# Sychronome_driver.net
KiCad netlist of a schematic drawn in EAGLE
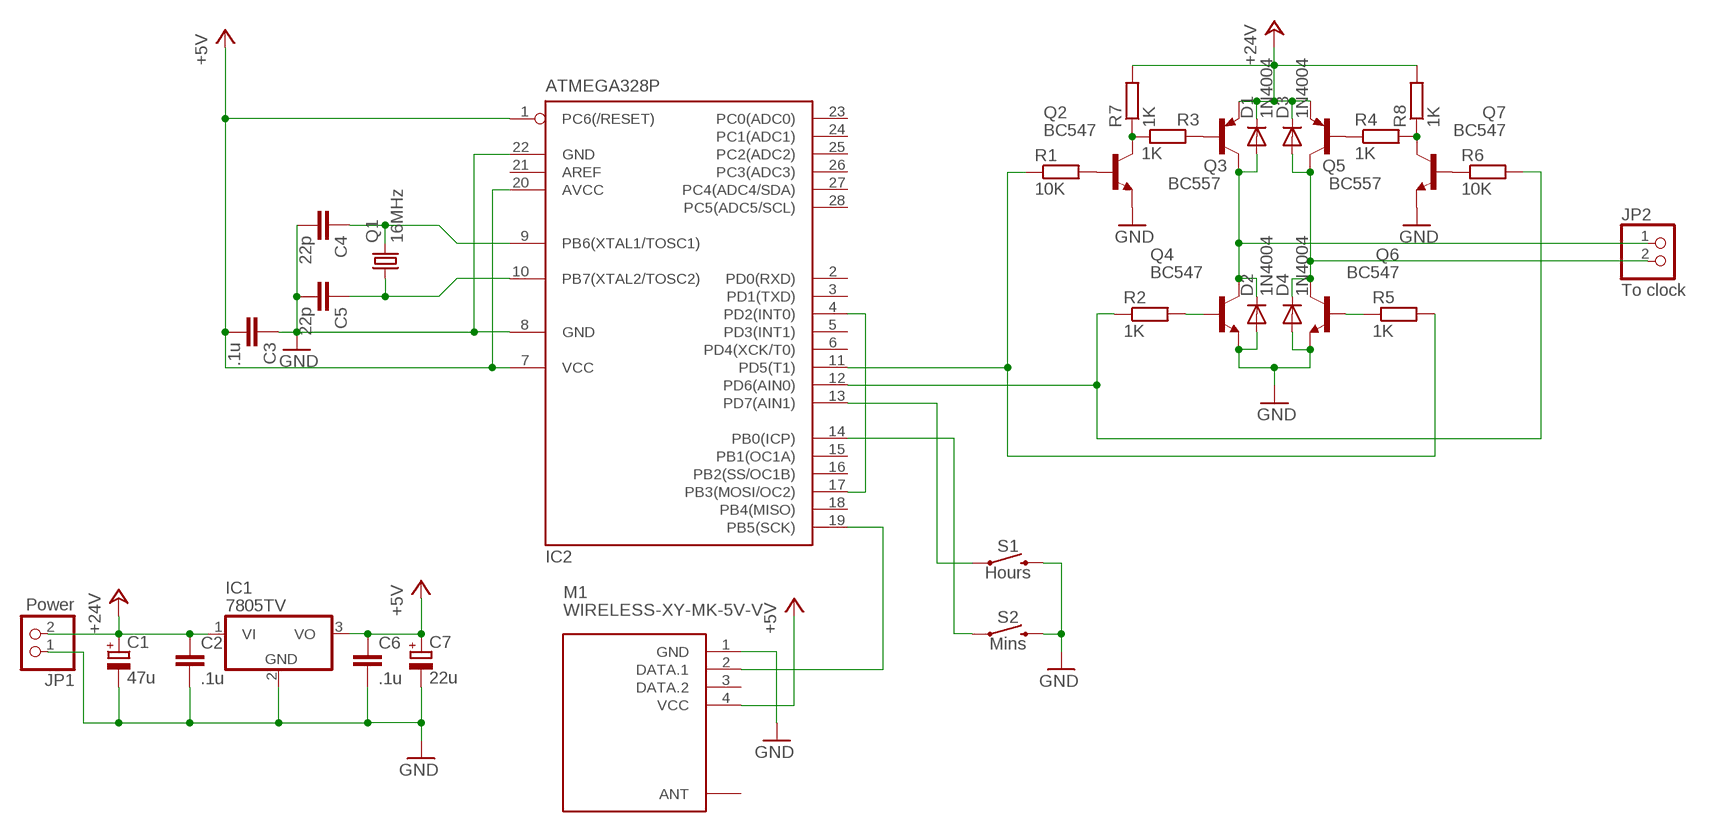
[diagram p0: schematic, sheet 1]

(export (version "E")
  (design (tool "Eeschema 10.0.6"))
  (components
    (comp (ref "C1")
      (value "47u")
      (footprint "eagle-import:E2,5-7")
      (libsource (lib "eagle-import") (part "CPOL-EUE2.5-7"))
    )
    (comp (ref "C2")
      (value ".1u")
      (footprint "eagle-import:C025-024X044")
      (libsource (lib "eagle-import") (part "C-EU025-024X044"))
    )
    (comp (ref "C3")
      (value ".1u")
      (footprint "eagle-import:C025-024X044")
      (libsource (lib "eagle-import") (part "C-EU025-024X044"))
    )
    (comp (ref "C4")
      (value "22p")
      (footprint "eagle-import:C025-024X044")
      (libsource (lib "eagle-import") (part "C-EU025-024X044"))
    )
    (comp (ref "C5")
      (value "22p")
      (footprint "eagle-import:C025-024X044")
      (libsource (lib "eagle-import") (part "C-EU025-024X044"))
    )
    (comp (ref "C6")
      (value ".1u")
      (footprint "eagle-import:C025-024X044")
      (libsource (lib "eagle-import") (part "C-EU025-024X044"))
    )
    (comp (ref "C7")
      (value "22u")
      (footprint "eagle-import:E2,5-7")
      (libsource (lib "eagle-import") (part "CPOL-EUE2.5-7"))
    )
    (comp (ref "D1")
      (value "1N4004")
      (footprint "eagle-import:DO41-10")
      (libsource (lib "eagle-import") (part "1N4004"))
    )
    (comp (ref "D2")
      (value "1N4004")
      (footprint "eagle-import:DO41-10")
      (libsource (lib "eagle-import") (part "1N4004"))
    )
    (comp (ref "D3")
      (value "1N4004")
      (footprint "eagle-import:DO41-10")
      (libsource (lib "eagle-import") (part "1N4004"))
    )
    (comp (ref "D4")
      (value "1N4004")
      (footprint "eagle-import:DO41-10")
      (libsource (lib "eagle-import") (part "1N4004"))
    )
    (comp (ref "IC1")
      (value "7805TV")
      (footprint "eagle-import:TO220V")
      (libsource (lib "eagle-import") (part "78TV05"))
    )
    (comp (ref "IC2")
      (value "ATMEGA328P")
      (footprint "eagle-import:DIL28-3")
      (libsource (lib "eagle-import") (part "MEGA8-P"))
    )
    (comp (ref "JP1")
      (value "Power")
      (footprint "eagle-import:1X02")
      (libsource (lib "eagle-import") (part "PINHD-1X2"))
    )
    (comp (ref "JP2")
      (value "To clock")
      (footprint "eagle-import:1X02")
      (libsource (lib "eagle-import") (part "PINHD-1X2"))
    )
    (comp (ref "M1")
      (value "WIRELESS-XY-MK-5V-V")
      (footprint "eagle-import:WIRELESS-XY-MK-5V#V")
      (libsource (lib "eagle-import") (part "WIRELESS-XY-MK-5V-V"))
    )
    (comp (ref "Q1")
      (value "16MHz")
      (footprint "eagle-import:HC49U-V")
      (libsource (lib "eagle-import") (part "CRYSTALHC49U-V"))
    )
    (comp (ref "Q2")
      (value "BC547")
      (footprint "eagle-import:TO92")
      (libsource (lib "eagle-import") (part "BC547"))
    )
    (comp (ref "Q3")
      (value "BC557")
      (footprint "eagle-import:TO92")
      (libsource (lib "eagle-import") (part "BC557"))
    )
    (comp (ref "Q4")
      (value "BC547")
      (footprint "eagle-import:TO92")
      (libsource (lib "eagle-import") (part "BC547"))
    )
    (comp (ref "Q5")
      (value "BC557")
      (footprint "eagle-import:TO92")
      (libsource (lib "eagle-import") (part "BC557"))
    )
    (comp (ref "Q6")
      (value "BC547")
      (footprint "eagle-import:TO92")
      (libsource (lib "eagle-import") (part "BC547"))
    )
    (comp (ref "Q7")
      (value "BC547")
      (footprint "eagle-import:TO92")
      (libsource (lib "eagle-import") (part "BC547"))
    )
    (comp (ref "R1")
      (value "10K")
      (footprint "eagle-import:0204_7")
      (libsource (lib "eagle-import") (part "R-EU_0204/7"))
    )
    (comp (ref "R2")
      (value "1K")
      (footprint "eagle-import:0204_7")
      (libsource (lib "eagle-import") (part "R-EU_0204/7"))
    )
    (comp (ref "R3")
      (value "1K")
      (footprint "eagle-import:0204_7")
      (libsource (lib "eagle-import") (part "R-EU_0204/7"))
    )
    (comp (ref "R4")
      (value "1K")
      (footprint "eagle-import:0204_7")
      (libsource (lib "eagle-import") (part "R-EU_0204/7"))
    )
    (comp (ref "R5")
      (value "1K")
      (footprint "eagle-import:0204_7")
      (libsource (lib "eagle-import") (part "R-EU_0204/7"))
    )
    (comp (ref "R6")
      (value "10K")
      (footprint "eagle-import:0204_7")
      (libsource (lib "eagle-import") (part "R-EU_0204/7"))
    )
    (comp (ref "R7")
      (value "1K")
      (footprint "eagle-import:0204_7")
      (libsource (lib "eagle-import") (part "R-EU_0204/7"))
    )
    (comp (ref "R8")
      (value "1K")
      (footprint "eagle-import:0204_7")
      (libsource (lib "eagle-import") (part "R-EU_0204/7"))
    )
    (comp (ref "S1")
      (value "Hours")
      (footprint "eagle-import:TACTILE_SWITCH_PTH_6.0MM")
      (libsource (lib "eagle-import") (part "MOMENTARY-SWITCH-SPST-PTH-6.0MM"))
    )
    (comp (ref "S2")
      (value "Mins")
      (footprint "eagle-import:TACTILE_SWITCH_PTH_6.0MM")
      (libsource (lib "eagle-import") (part "MOMENTARY-SWITCH-SPST-PTH-6.0MM"))
    )
  )
  (nets
    (net (code "1") (name "+5V") (class "Default")
      (node (ref "C3") (pin "2") (pinfunction "2_2") (pintype "passive"))
      (node (ref "C6") (pin "1") (pinfunction "1_1") (pintype "passive"))
      (node (ref "C7") (pin "+") (pinfunction "+_+") (pintype "passive"))
      (node (ref "IC1") (pin "3") (pinfunction "VO_3") (pintype "passive"))
      (node (ref "IC2") (pin "1") (pinfunction "PC6(/RESET)_1") (pintype "bidirectional"))
      (node (ref "IC2") (pin "20") (pinfunction "AVCC_20") (pintype "power_in"))
      (node (ref "IC2") (pin "7") (pinfunction "VCC_7") (pintype "power_in"))
      (node (ref "M1") (pin "4") (pinfunction "VCC_4") (pintype "bidirectional"))
    )
    (net (code "2") (name "+24V") (class "Default")
      (node (ref "C1") (pin "+") (pinfunction "+_+") (pintype "passive"))
      (node (ref "C2") (pin "1") (pinfunction "1_1") (pintype "passive"))
      (node (ref "D1") (pin "C") (pinfunction "C_C") (pintype "passive"))
      (node (ref "D3") (pin "C") (pinfunction "C_C") (pintype "passive"))
      (node (ref "IC1") (pin "1") (pinfunction "VI_1") (pintype "input"))
      (node (ref "JP1") (pin "2") (pinfunction "2_2") (pintype "passive"))
      (node (ref "Q3") (pin "1") (pinfunction "E_1") (pintype "passive"))
      (node (ref "Q5") (pin "1") (pinfunction "E_1") (pintype "passive"))
      (node (ref "R7") (pin "2") (pinfunction "2_2") (pintype "passive"))
      (node (ref "R8") (pin "2") (pinfunction "2_2") (pintype "passive"))
    )
    (net (code "3") (name "GND") (class "Default")
      (node (ref "C1") (pin "-") (pinfunction "-_-") (pintype "passive"))
      (node (ref "C2") (pin "2") (pinfunction "2_2") (pintype "passive"))
      (node (ref "C3") (pin "1") (pinfunction "1_1") (pintype "passive"))
      (node (ref "C4") (pin "2") (pinfunction "2_2") (pintype "passive"))
      (node (ref "C5") (pin "2") (pinfunction "2_2") (pintype "passive"))
      (node (ref "C6") (pin "2") (pinfunction "2_2") (pintype "passive"))
      (node (ref "C7") (pin "-") (pinfunction "-_-") (pintype "passive"))
      (node (ref "D2") (pin "A") (pinfunction "A_A") (pintype "passive"))
      (node (ref "D4") (pin "A") (pinfunction "A_A") (pintype "passive"))
      (node (ref "IC1") (pin "2") (pinfunction "GND_2") (pintype "passive"))
      (node (ref "IC2") (pin "22") (pinfunction "GND_22") (pintype "power_in"))
      (node (ref "IC2") (pin "8") (pinfunction "GND_8") (pintype "power_in"))
      (node (ref "JP1") (pin "1") (pinfunction "1_1") (pintype "passive"))
      (node (ref "M1") (pin "1") (pinfunction "GND_1") (pintype "bidirectional"))
      (node (ref "Q2") (pin "1") (pinfunction "E_1") (pintype "passive"))
      (node (ref "Q4") (pin "1") (pinfunction "E_1") (pintype "passive"))
      (node (ref "Q6") (pin "1") (pinfunction "E_1") (pintype "passive"))
      (node (ref "Q7") (pin "1") (pinfunction "E_1") (pintype "passive"))
      (node (ref "S1") (pin "3") (pinfunction "2_3") (pintype "passive"))
      (node (ref "S2") (pin "3") (pinfunction "2_3") (pintype "passive"))
    )
    (net (code "4") (name "Net-(IC2-PB0(ICP))") (class "Default")
      (node (ref "IC2") (pin "14") (pinfunction "PB0(ICP)_14") (pintype "bidirectional"))
      (node (ref "S2") (pin "1") (pinfunction "1_1") (pintype "passive"))
    )
    (net (code "5") (name "Net-(IC2-PB3(MOSI{slash}OC2))") (class "Default")
      (node (ref "IC2") (pin "17") (pinfunction "PB3(MOSI/OC2)_17") (pintype "bidirectional"))
      (node (ref "IC2") (pin "4") (pinfunction "PD2(INT0)_4") (pintype "bidirectional"))
    )
    (net (code "6") (name "Net-(IC2-PB5(SCK))") (class "Default")
      (node (ref "IC2") (pin "19") (pinfunction "PB5(SCK)_19") (pintype "bidirectional"))
      (node (ref "M1") (pin "2") (pinfunction "DATA.1_2") (pintype "bidirectional"))
    )
    (net (code "7") (name "Net-(IC2-PB6(XTAL1{slash}TOSC1))") (class "Default")
      (node (ref "C4") (pin "1") (pinfunction "1_1") (pintype "passive"))
      (node (ref "IC2") (pin "9") (pinfunction "PB6(XTAL1/TOSC1)_9") (pintype "bidirectional"))
      (node (ref "Q1") (pin "2") (pinfunction "2_2") (pintype "passive"))
    )
    (net (code "8") (name "Net-(IC2-PB7(XTAL2{slash}TOSC2))") (class "Default")
      (node (ref "C5") (pin "1") (pinfunction "1_1") (pintype "passive"))
      (node (ref "IC2") (pin "10") (pinfunction "PB7(XTAL2/TOSC2)_10") (pintype "bidirectional"))
      (node (ref "Q1") (pin "1") (pinfunction "1_1") (pintype "passive"))
    )
    (net (code "9") (name "Net-(IC2-PD5(T1))") (class "Default")
      (node (ref "IC2") (pin "11") (pinfunction "PD5(T1)_11") (pintype "bidirectional"))
      (node (ref "R1") (pin "1") (pinfunction "1_1") (pintype "passive"))
      (node (ref "R5") (pin "2") (pinfunction "2_2") (pintype "passive"))
    )
    (net (code "10") (name "Net-(IC2-PD6(AIN0))") (class "Default")
      (node (ref "IC2") (pin "12") (pinfunction "PD6(AIN0)_12") (pintype "bidirectional"))
      (node (ref "R2") (pin "1") (pinfunction "1_1") (pintype "passive"))
      (node (ref "R6") (pin "2") (pinfunction "2_2") (pintype "passive"))
    )
    (net (code "11") (name "Net-(IC2-PD7(AIN1))") (class "Default")
      (node (ref "IC2") (pin "13") (pinfunction "PD7(AIN1)_13") (pintype "bidirectional"))
      (node (ref "S1") (pin "1") (pinfunction "1_1") (pintype "passive"))
    )
    (net (code "12") (name "Net-(Q2-B)") (class "Default")
      (node (ref "Q2") (pin "2") (pinfunction "B_2") (pintype "passive"))
      (node (ref "R1") (pin "2") (pinfunction "2_2") (pintype "passive"))
    )
    (net (code "13") (name "Net-(Q2-C)") (class "Default")
      (node (ref "Q2") (pin "3") (pinfunction "C_3") (pintype "passive"))
      (node (ref "R3") (pin "1") (pinfunction "1_1") (pintype "passive"))
      (node (ref "R7") (pin "1") (pinfunction "1_1") (pintype "passive"))
    )
    (net (code "14") (name "Net-(Q3-B)") (class "Default")
      (node (ref "Q3") (pin "2") (pinfunction "B_2") (pintype "passive"))
      (node (ref "R3") (pin "2") (pinfunction "2_2") (pintype "passive"))
    )
    (net (code "15") (name "Net-(Q3-C)") (class "Default")
      (node (ref "D1") (pin "A") (pinfunction "A_A") (pintype "passive"))
      (node (ref "D2") (pin "C") (pinfunction "C_C") (pintype "passive"))
      (node (ref "JP2") (pin "1") (pinfunction "1_1") (pintype "passive"))
      (node (ref "Q3") (pin "3") (pinfunction "C_3") (pintype "passive"))
      (node (ref "Q4") (pin "3") (pinfunction "C_3") (pintype "passive"))
    )
    (net (code "16") (name "Net-(Q4-B)") (class "Default")
      (node (ref "Q4") (pin "2") (pinfunction "B_2") (pintype "passive"))
      (node (ref "R2") (pin "2") (pinfunction "2_2") (pintype "passive"))
    )
    (net (code "17") (name "Net-(Q5-B)") (class "Default")
      (node (ref "Q5") (pin "2") (pinfunction "B_2") (pintype "passive"))
      (node (ref "R4") (pin "1") (pinfunction "1_1") (pintype "passive"))
    )
    (net (code "18") (name "Net-(Q5-C)") (class "Default")
      (node (ref "D3") (pin "A") (pinfunction "A_A") (pintype "passive"))
      (node (ref "D4") (pin "C") (pinfunction "C_C") (pintype "passive"))
      (node (ref "JP2") (pin "2") (pinfunction "2_2") (pintype "passive"))
      (node (ref "Q5") (pin "3") (pinfunction "C_3") (pintype "passive"))
      (node (ref "Q6") (pin "3") (pinfunction "C_3") (pintype "passive"))
    )
    (net (code "19") (name "Net-(Q6-B)") (class "Default")
      (node (ref "Q6") (pin "2") (pinfunction "B_2") (pintype "passive"))
      (node (ref "R5") (pin "1") (pinfunction "1_1") (pintype "passive"))
    )
    (net (code "20") (name "Net-(Q7-B)") (class "Default")
      (node (ref "Q7") (pin "2") (pinfunction "B_2") (pintype "passive"))
      (node (ref "R6") (pin "1") (pinfunction "1_1") (pintype "passive"))
    )
    (net (code "21") (name "Net-(Q7-C)") (class "Default")
      (node (ref "Q7") (pin "3") (pinfunction "C_3") (pintype "passive"))
      (node (ref "R4") (pin "2") (pinfunction "2_2") (pintype "passive"))
      (node (ref "R8") (pin "1") (pinfunction "1_1") (pintype "passive"))
    )
    (net (code "22") (name "unconnected-(IC2-AREF-Pad21)") (class "Default")
      (node (ref "IC2") (pin "21") (pinfunction "AREF_21") (pintype "passive"))
    )
    (net (code "23") (name "unconnected-(IC2-PB1(OC1A)-Pad15)") (class "Default")
      (node (ref "IC2") (pin "15") (pinfunction "PB1(OC1A)_15") (pintype "bidirectional"))
    )
    (net (code "24") (name "unconnected-(IC2-PB2(SS{slash}OC1B)-Pad16)") (class "Default")
      (node (ref "IC2") (pin "16") (pinfunction "PB2(SS/OC1B)_16") (pintype "bidirectional"))
    )
    (net (code "25") (name "unconnected-(IC2-PB4(MISO)-Pad18)") (class "Default")
      (node (ref "IC2") (pin "18") (pinfunction "PB4(MISO)_18") (pintype "bidirectional"))
    )
    (net (code "26") (name "unconnected-(IC2-PC0(ADC0)-Pad23)") (class "Default")
      (node (ref "IC2") (pin "23") (pinfunction "PC0(ADC0)_23") (pintype "bidirectional"))
    )
    (net (code "27") (name "unconnected-(IC2-PC1(ADC1)-Pad24)") (class "Default")
      (node (ref "IC2") (pin "24") (pinfunction "PC1(ADC1)_24") (pintype "bidirectional"))
    )
    (net (code "28") (name "unconnected-(IC2-PC2(ADC2)-Pad25)") (class "Default")
      (node (ref "IC2") (pin "25") (pinfunction "PC2(ADC2)_25") (pintype "bidirectional"))
    )
    (net (code "29") (name "unconnected-(IC2-PC3(ADC3)-Pad26)") (class "Default")
      (node (ref "IC2") (pin "26") (pinfunction "PC3(ADC3)_26") (pintype "bidirectional"))
    )
    (net (code "30") (name "unconnected-(IC2-PC4(ADC4{slash}SDA)-Pad27)") (class "Default")
      (node (ref "IC2") (pin "27") (pinfunction "PC4(ADC4/SDA)_27") (pintype "bidirectional"))
    )
    (net (code "31") (name "unconnected-(IC2-PC5(ADC5{slash}SCL)-Pad28)") (class "Default")
      (node (ref "IC2") (pin "28") (pinfunction "PC5(ADC5/SCL)_28") (pintype "bidirectional"))
    )
    (net (code "32") (name "unconnected-(IC2-PD0(RXD)-Pad2)") (class "Default")
      (node (ref "IC2") (pin "2") (pinfunction "PD0(RXD)_2") (pintype "bidirectional"))
    )
    (net (code "33") (name "unconnected-(IC2-PD1(TXD)-Pad3)") (class "Default")
      (node (ref "IC2") (pin "3") (pinfunction "PD1(TXD)_3") (pintype "bidirectional"))
    )
    (net (code "34") (name "unconnected-(IC2-PD3(INT1)-Pad5)") (class "Default")
      (node (ref "IC2") (pin "5") (pinfunction "PD3(INT1)_5") (pintype "bidirectional"))
    )
    (net (code "35") (name "unconnected-(IC2-PD4(XCK{slash}T0)-Pad6)") (class "Default")
      (node (ref "IC2") (pin "6") (pinfunction "PD4(XCK/T0)_6") (pintype "bidirectional"))
    )
    (net (code "36") (name "unconnected-(M1-DATA.2-Pad3)") (class "Default")
      (node (ref "M1") (pin "3") (pinfunction "DATA.2_3") (pintype "bidirectional"))
    )
    (net (code "37") (name "unconnected-(M1-PadANT)") (class "Default")
      (node (ref "M1") (pin "ANT") (pinfunction "ANT_ANT") (pintype "output"))
    )
  )
)
